# BW1098FFC_MIPI_CAM.net
KiCad netlist of a schematic drawn in Altium Designer
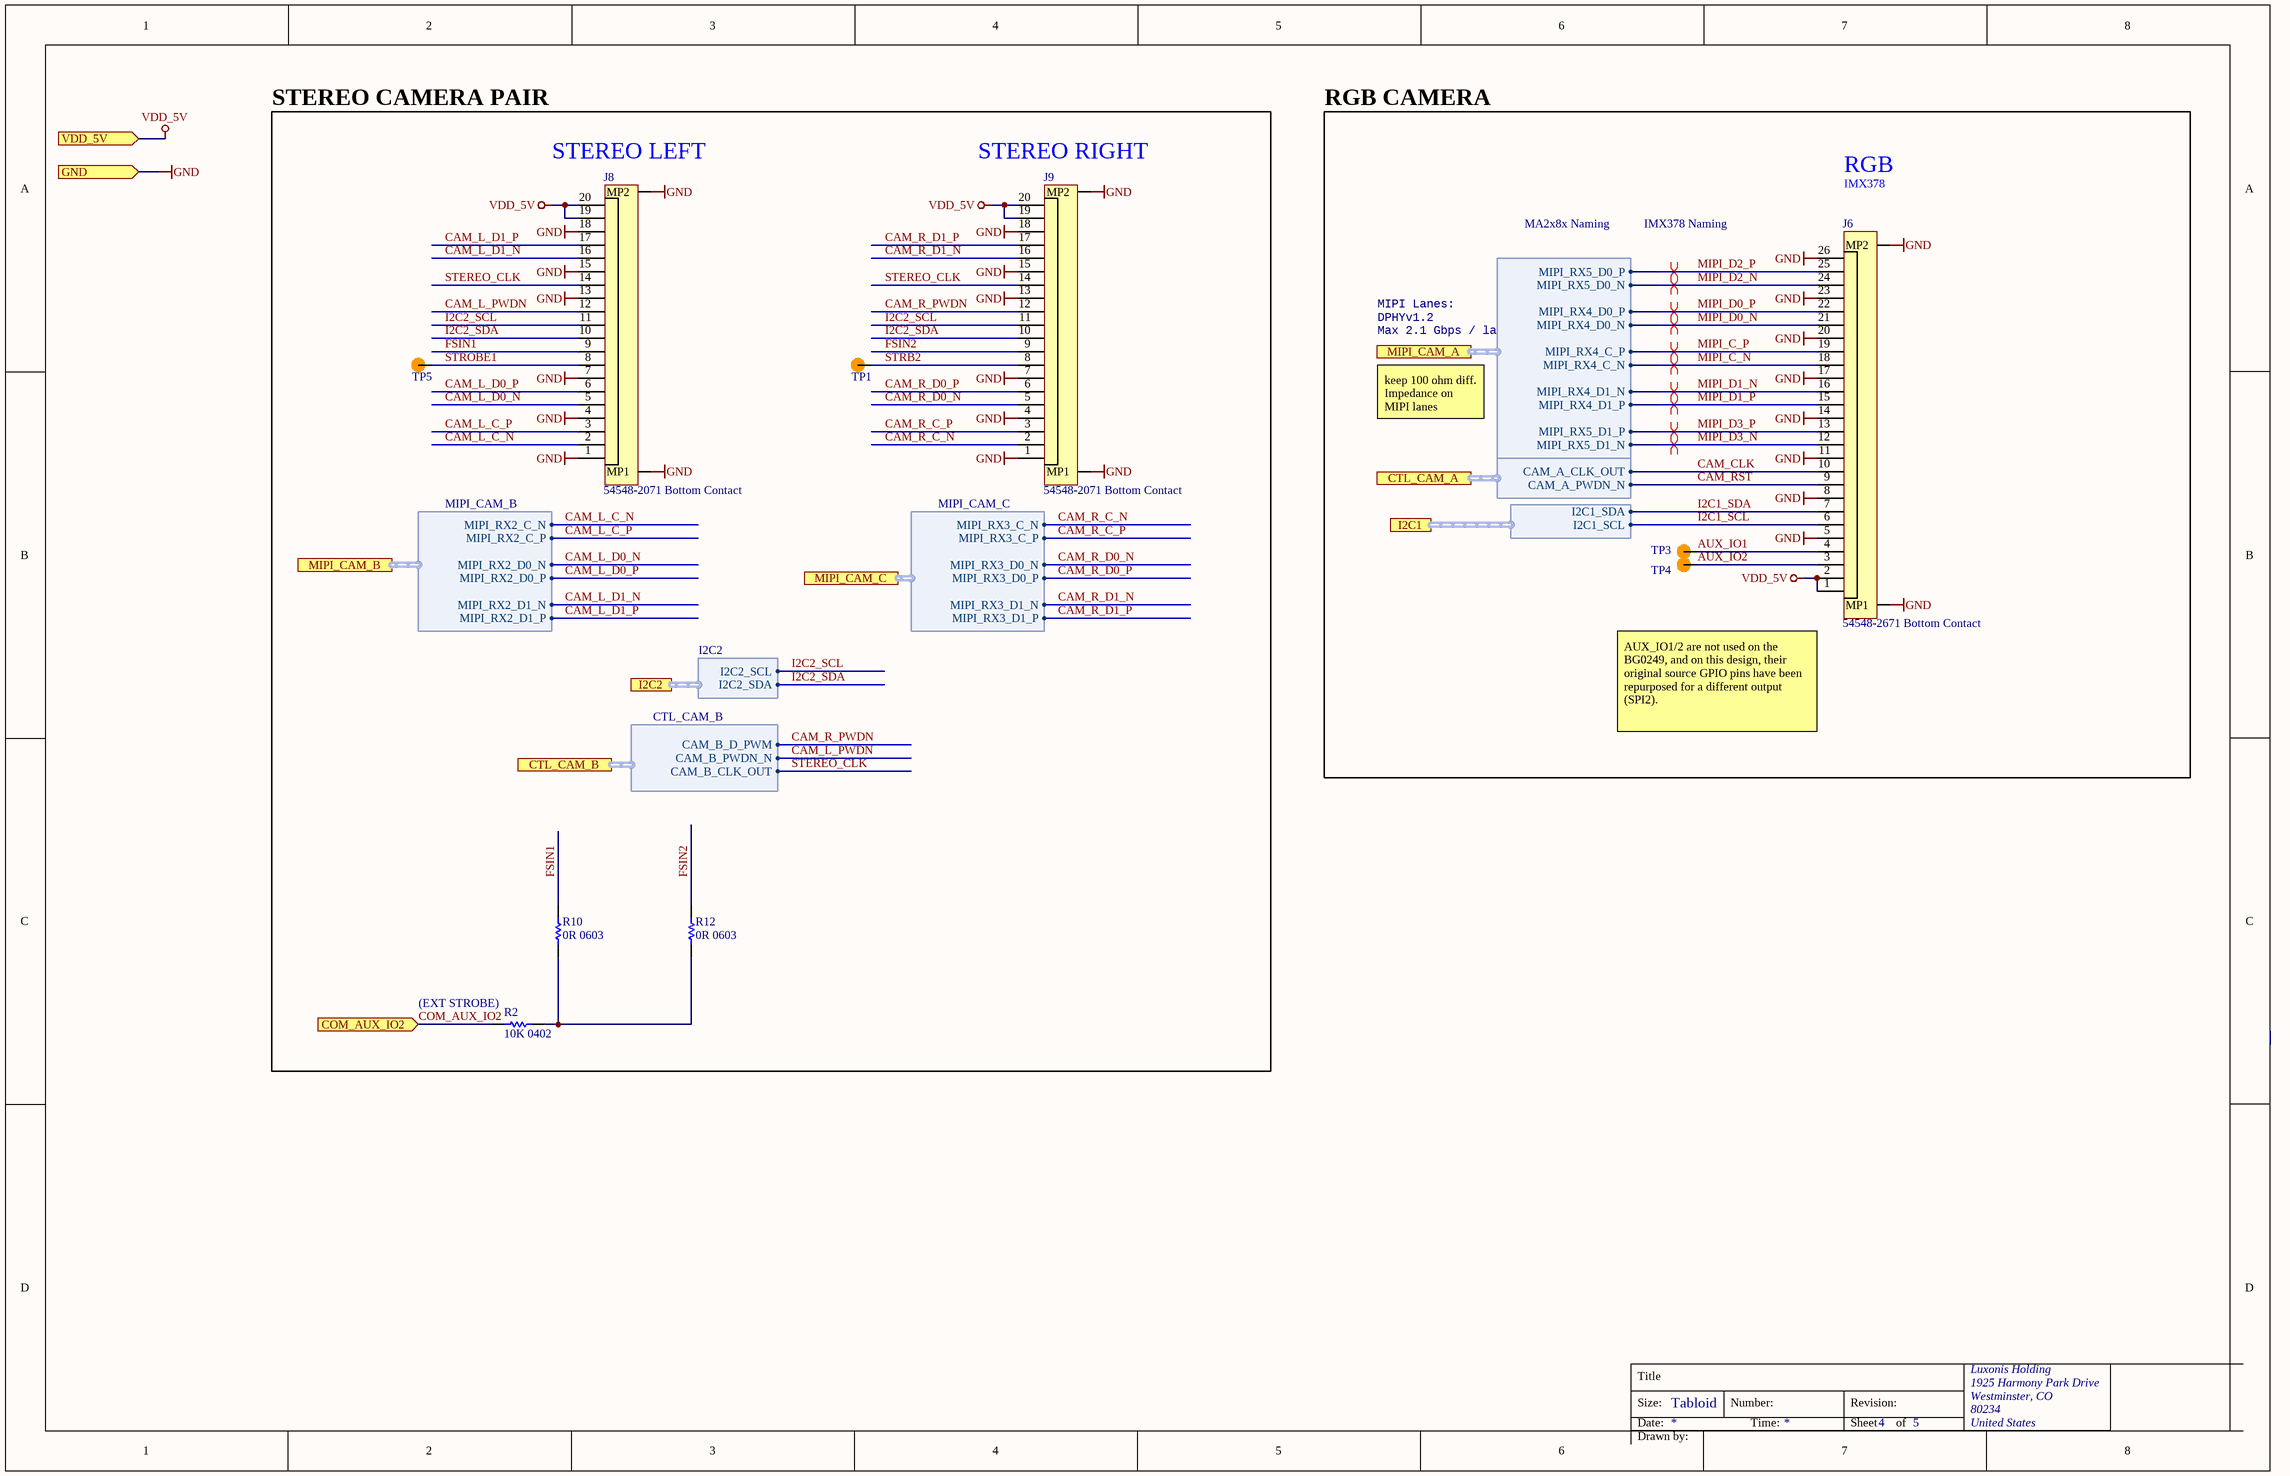
[diagram p0: BW1098FFC_MIPI_CAM.SchDoc]

(export (version "E")
  (design (tool "Eeschema 10.0.6"))
  (components
    (comp (ref "J6")
      (value "54548-2671 Bottom Contact")
      (footprint "LuxonisMaster:54548-2671")
      (fields
        (field (name "MANUFACTURER_PART_NUMBER") "54548-2671")
        (field (name "MOUSER PART NUMBER") "538-54548-2671")
      )
      (libsource (lib "LuxonisMaster") (part "54548-2671"))
    )
    (comp (ref "J8")
      (value "54548-2071 Bottom Contact")
      (footprint "LuxonisMaster:54548-2071")
      (fields
        (field (name "MANUFACTURER_PART_NUMBER") "54548-2071")
        (field (name "MOUSER PART NUMBER") "538-54548-2071")
      )
      (libsource (lib "LuxonisMaster") (part "54548-2071"))
    )
    (comp (ref "J9")
      (value "54548-2071 Bottom Contact")
      (footprint "LuxonisMaster:54548-2071")
      (fields
        (field (name "MANUFACTURER_PART_NUMBER") "54548-2071")
        (field (name "MOUSER PART NUMBER") "538-54548-2071")
      )
      (libsource (lib "LuxonisMaster") (part "54548-2071"))
    )
    (comp (ref "R2")
      (value "10K 0402")
      (footprint "RES_Altium_Vault_Generic:RESC0402(1005)_N")
      (fields (field (name "TOLERANCE") "1%"))
      (libsource (lib "LuxonisMaster") (part "RC0402FR-1310KL"))
    )
    (comp (ref "R10")
      (value "0R 0603")
      (footprint "RES_Altium_Vault_Generic:RESC0603(1608)_N")
      (fields (field (name "TOLERANCE") "5%"))
      (libsource (lib "LuxonisMaster") (part "CRCW06030000Z0EA"))
    )
    (comp (ref "R12")
      (value "0R 0603")
      (footprint "RES_Altium_Vault_Generic:RESC0603(1608)_N")
      (fields (field (name "TOLERANCE") "5%"))
      (libsource (lib "LuxonisMaster") (part "CRCW06030000Z0EA"))
    )
    (comp (ref "TP1")
      (value "TP100_200_NS")
      (footprint "LuxonisMaster:TP100_200_NS")
      (libsource (lib "LuxonisMaster") (part "TEST_POINT"))
    )
    (comp (ref "TP3")
      (value "TP100_200_NS")
      (footprint "LuxonisMaster:TP100_200_NS")
      (libsource (lib "LuxonisMaster") (part "TEST_POINT"))
    )
    (comp (ref "TP4")
      (value "TP100_200_NS")
      (footprint "LuxonisMaster:TP100_200_NS")
      (libsource (lib "LuxonisMaster") (part "TEST_POINT"))
    )
    (comp (ref "TP5")
      (value "TP100_200_NS")
      (footprint "LuxonisMaster:TP100_200_NS")
      (libsource (lib "LuxonisMaster") (part "TEST_POINT"))
    )
  )
  (nets
    (net (code "8") (name "/AUX_IO1") (class "Default")
      (node (ref "J6") (pin "4") (pinfunction "4_4") (pintype "passive"))
      (node (ref "TP3") (pin "1") (pintype "passive"))
    )
    (net (code "9") (name "/AUX_IO2") (class "Default")
      (node (ref "J6") (pin "3") (pinfunction "3_3") (pintype "passive"))
      (node (ref "TP4") (pin "1") (pintype "passive"))
    )
    (net (code "10") (name "/CAM_CLK") (class "Default")
      (node (ref "J6") (pin "10") (pinfunction "10_10") (pintype "passive"))
    )
    (net (code "11") (name "/CAM_L_C_N") (class "Default")
      (node (ref "J8") (pin "2") (pinfunction "2_2") (pintype "passive"))
    )
    (net (code "12") (name "/CAM_L_C_P") (class "Default")
      (node (ref "J8") (pin "3") (pinfunction "3_3") (pintype "passive"))
    )
    (net (code "13") (name "/CAM_L_D0_N") (class "Default")
      (node (ref "J8") (pin "5") (pinfunction "5_5") (pintype "passive"))
    )
    (net (code "14") (name "/CAM_L_D0_P") (class "Default")
      (node (ref "J8") (pin "6") (pinfunction "6_6") (pintype "passive"))
    )
    (net (code "15") (name "/CAM_L_D1_N") (class "Default")
      (node (ref "J8") (pin "16") (pinfunction "16_16") (pintype "passive"))
    )
    (net (code "16") (name "/CAM_L_D1_P") (class "Default")
      (node (ref "J8") (pin "17") (pinfunction "17_17") (pintype "passive"))
    )
    (net (code "17") (name "/CAM_L_PWDN") (class "Default")
      (node (ref "J8") (pin "12") (pinfunction "12_12") (pintype "passive"))
    )
    (net (code "18") (name "/CAM_RST") (class "Default")
      (node (ref "J6") (pin "9") (pinfunction "9_9") (pintype "passive"))
    )
    (net (code "19") (name "/CAM_R_C_N") (class "Default")
      (node (ref "J9") (pin "2") (pinfunction "2_2") (pintype "passive"))
    )
    (net (code "20") (name "/CAM_R_C_P") (class "Default")
      (node (ref "J9") (pin "3") (pinfunction "3_3") (pintype "passive"))
    )
    (net (code "21") (name "/CAM_R_D0_N") (class "Default")
      (node (ref "J9") (pin "5") (pinfunction "5_5") (pintype "passive"))
    )
    (net (code "22") (name "/CAM_R_D0_P") (class "Default")
      (node (ref "J9") (pin "6") (pinfunction "6_6") (pintype "passive"))
    )
    (net (code "23") (name "/CAM_R_D1_N") (class "Default")
      (node (ref "J9") (pin "16") (pinfunction "16_16") (pintype "passive"))
    )
    (net (code "24") (name "/CAM_R_D1_P") (class "Default")
      (node (ref "J9") (pin "17") (pinfunction "17_17") (pintype "passive"))
    )
    (net (code "25") (name "/CAM_R_PWDN") (class "Default")
      (node (ref "J9") (pin "12") (pinfunction "12_12") (pintype "passive"))
    )
    (net (code "26") (name "/COM_AUX_IO2") (class "Default")
      (node (ref "R2") (pin "1") (pinfunction "1_1") (pintype "passive"))
    )
    (net (code "28") (name "/FSIN1") (class "Default")
      (node (ref "J8") (pin "9") (pinfunction "9_9") (pintype "passive"))
      (node (ref "R10") (pin "2") (pinfunction "2_2") (pintype "passive"))
    )
    (net (code "29") (name "/FSIN2") (class "Default")
      (node (ref "J9") (pin "9") (pinfunction "9_9") (pintype "passive"))
      (node (ref "R12") (pin "2") (pinfunction "2_2") (pintype "passive"))
    )
    (net (code "30") (name "/I2C1_SCL") (class "Default")
      (node (ref "J6") (pin "6") (pinfunction "6_6") (pintype "passive"))
    )
    (net (code "31") (name "/I2C1_SDA") (class "Default")
      (node (ref "J6") (pin "7") (pinfunction "7_7") (pintype "passive"))
    )
    (net (code "32") (name "/I2C2_SCL") (class "Default")
      (node (ref "J8") (pin "11") (pinfunction "11_11") (pintype "passive"))
      (node (ref "J9") (pin "11") (pinfunction "11_11") (pintype "passive"))
    )
    (net (code "33") (name "/I2C2_SDA") (class "Default")
      (node (ref "J8") (pin "10") (pinfunction "10_10") (pintype "passive"))
      (node (ref "J9") (pin "10") (pinfunction "10_10") (pintype "passive"))
    )
    (net (code "34") (name "/MIPI_C_N") (class "Default")
      (node (ref "J6") (pin "18") (pinfunction "18_18") (pintype "passive"))
    )
    (net (code "35") (name "/MIPI_C_P") (class "Default")
      (node (ref "J6") (pin "19") (pinfunction "19_19") (pintype "passive"))
    )
    (net (code "36") (name "/MIPI_D0_N") (class "Default")
      (node (ref "J6") (pin "21") (pinfunction "21_21") (pintype "passive"))
    )
    (net (code "37") (name "/MIPI_D0_P") (class "Default")
      (node (ref "J6") (pin "22") (pinfunction "22_22") (pintype "passive"))
    )
    (net (code "38") (name "/MIPI_D1_N") (class "Default")
      (node (ref "J6") (pin "16") (pinfunction "16_16") (pintype "passive"))
    )
    (net (code "39") (name "/MIPI_D1_P") (class "Default")
      (node (ref "J6") (pin "15") (pinfunction "15_15") (pintype "passive"))
    )
    (net (code "40") (name "/MIPI_D2_N") (class "Default")
      (node (ref "J6") (pin "24") (pinfunction "24_24") (pintype "passive"))
    )
    (net (code "41") (name "/MIPI_D2_P") (class "Default")
      (node (ref "J6") (pin "25") (pinfunction "25_25") (pintype "passive"))
    )
    (net (code "42") (name "/MIPI_D3_N") (class "Default")
      (node (ref "J6") (pin "12") (pinfunction "12_12") (pintype "passive"))
    )
    (net (code "43") (name "/MIPI_D3_P") (class "Default")
      (node (ref "J6") (pin "13") (pinfunction "13_13") (pintype "passive"))
    )
    (net (code "44") (name "/STEREO_CLK") (class "Default")
      (node (ref "J8") (pin "14") (pinfunction "14_14") (pintype "passive"))
      (node (ref "J9") (pin "14") (pinfunction "14_14") (pintype "passive"))
    )
    (net (code "45") (name "/STRB2") (class "Default")
      (node (ref "J9") (pin "8") (pinfunction "8_8") (pintype "passive"))
      (node (ref "TP1") (pin "1") (pintype "passive"))
    )
    (net (code "46") (name "/STROBE1") (class "Default")
      (node (ref "J8") (pin "8") (pinfunction "8_8") (pintype "passive"))
      (node (ref "TP5") (pin "1") (pintype "passive"))
    )
    (net (code "53") (name "GND") (class "Default")
      (node (ref "J6") (pin "11") (pinfunction "11_11") (pintype "passive"))
      (node (ref "J6") (pin "14") (pinfunction "14_14") (pintype "passive"))
      (node (ref "J6") (pin "17") (pinfunction "17_17") (pintype "passive"))
      (node (ref "J6") (pin "20") (pinfunction "20_20") (pintype "passive"))
      (node (ref "J6") (pin "23") (pinfunction "23_23") (pintype "passive"))
      (node (ref "J6") (pin "26") (pinfunction "26_26") (pintype "passive"))
      (node (ref "J6") (pin "5") (pinfunction "5_5") (pintype "passive"))
      (node (ref "J6") (pin "8") (pinfunction "8_8") (pintype "passive"))
      (node (ref "J6") (pin "MP1") (pinfunction "MP1_MP1") (pintype "passive"))
      (node (ref "J6") (pin "MP2") (pinfunction "MP2_MP2") (pintype "passive"))
      (node (ref "J8") (pin "1") (pinfunction "1_1") (pintype "passive"))
      (node (ref "J8") (pin "13") (pinfunction "13_13") (pintype "passive"))
      (node (ref "J8") (pin "15") (pinfunction "15_15") (pintype "passive"))
      (node (ref "J8") (pin "18") (pinfunction "18_18") (pintype "passive"))
      (node (ref "J8") (pin "4") (pinfunction "4_4") (pintype "passive"))
      (node (ref "J8") (pin "7") (pinfunction "7_7") (pintype "passive"))
      (node (ref "J8") (pin "MP1") (pinfunction "MP1_MP1") (pintype "passive"))
      (node (ref "J8") (pin "MP2") (pinfunction "MP2_MP2") (pintype "passive"))
      (node (ref "J9") (pin "1") (pinfunction "1_1") (pintype "passive"))
      (node (ref "J9") (pin "13") (pinfunction "13_13") (pintype "passive"))
      (node (ref "J9") (pin "15") (pinfunction "15_15") (pintype "passive"))
      (node (ref "J9") (pin "18") (pinfunction "18_18") (pintype "passive"))
      (node (ref "J9") (pin "4") (pinfunction "4_4") (pintype "passive"))
      (node (ref "J9") (pin "7") (pinfunction "7_7") (pintype "passive"))
      (node (ref "J9") (pin "MP1") (pinfunction "MP1_MP1") (pintype "passive"))
      (node (ref "J9") (pin "MP2") (pinfunction "MP2_MP2") (pintype "passive"))
    )
    (net (code "54") (name "Net-(R10-Pad1)") (class "Default")
      (node (ref "R10") (pin "1") (pinfunction "1_1") (pintype "passive"))
      (node (ref "R12") (pin "1") (pinfunction "1_1") (pintype "passive"))
      (node (ref "R2") (pin "2") (pinfunction "2_2") (pintype "passive"))
    )
    (net (code "55") (name "VDD_5V") (class "Default")
      (node (ref "J6") (pin "1") (pinfunction "1_1") (pintype "passive"))
      (node (ref "J6") (pin "2") (pinfunction "2_2") (pintype "passive"))
      (node (ref "J8") (pin "19") (pinfunction "19_19") (pintype "passive"))
      (node (ref "J8") (pin "20") (pinfunction "20_20") (pintype "passive"))
      (node (ref "J9") (pin "19") (pinfunction "19_19") (pintype "passive"))
      (node (ref "J9") (pin "20") (pinfunction "20_20") (pintype "passive"))
    )
  )
)
